# LED_PCB.net
KiCad netlist of a schematic drawn in EAGLE
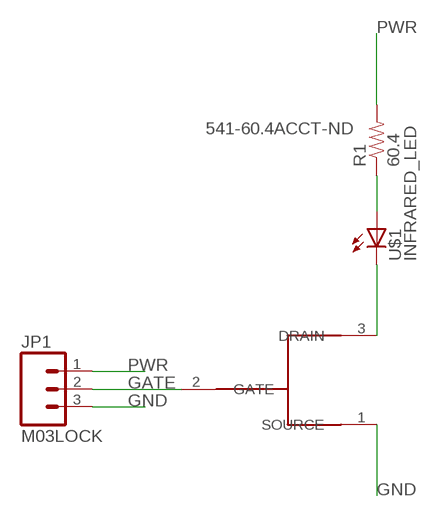
[diagram p0: schematic, sheet 1]

(export (version "E")
  (design (tool "Eeschema 10.0.6"))
  (components
    (comp (ref "JP1")
      (value "M03LOCK")
      (footprint "eagle-import:1X03_LOCK")
      (libsource (lib "eagle-import") (part "M03LOCK"))
    )
    (comp (ref "R1")
      (value "60.4")
      (footprint "eagle-import:R2010")
      (fields (field (name "DIGIKEY_PART") "541-60.4ACCT-ND "))
      (libsource (lib "eagle-import") (part "RESISTOR2010"))
    )
    (comp (ref "U$1")
      (value "INFRARED_LED")
      (footprint "eagle-import:MINI_MIDLED")
      (libsource (lib "eagle-import") (part "INFRARED_LED"))
    )
    (comp (ref "U$2")
      (value "N-CH_MOSFET")
      (footprint "eagle-import:SOT-416")
      (fields (field (name "DIGIKEY_PART") "2SK3019TLCT-ND") (field (name "PART_NUMBER") "2SK3019TL"))
      (libsource (lib "eagle-import") (part "N-CH_MOSFET"))
    )
  )
  (nets
    (net (code "1") (name "/GATE") (class "Default")
      (node (ref "JP1") (pin "2") (pinfunction "2_2") (pintype "passive"))
      (node (ref "U$2") (pin "2") (pinfunction "GATE_2") (pintype "bidirectional"))
    )
    (net (code "2") (name "/GND") (class "Default")
      (node (ref "JP1") (pin "3") (pinfunction "3_3") (pintype "passive"))
      (node (ref "U$2") (pin "1") (pinfunction "SOURCE_1") (pintype "bidirectional"))
    )
    (net (code "3") (name "/PWR") (class "Default")
      (node (ref "JP1") (pin "1") (pinfunction "1_1") (pintype "passive"))
      (node (ref "R1") (pin "2") (pinfunction "2_2") (pintype "passive"))
    )
    (net (code "4") (name "Net-(U$1-A)") (class "Default")
      (node (ref "R1") (pin "1") (pinfunction "1_1") (pintype "passive"))
      (node (ref "U$1") (pin "1") (pinfunction "A_1") (pintype "passive"))
    )
    (net (code "5") (name "Net-(U$1-C)") (class "Default")
      (node (ref "U$1") (pin "2") (pinfunction "C_2") (pintype "passive"))
      (node (ref "U$2") (pin "3") (pinfunction "DRAIN_3") (pintype "bidirectional"))
    )
  )
)
